# mml_matrix.net
KiCad netlist of a schematic drawn in EAGLE
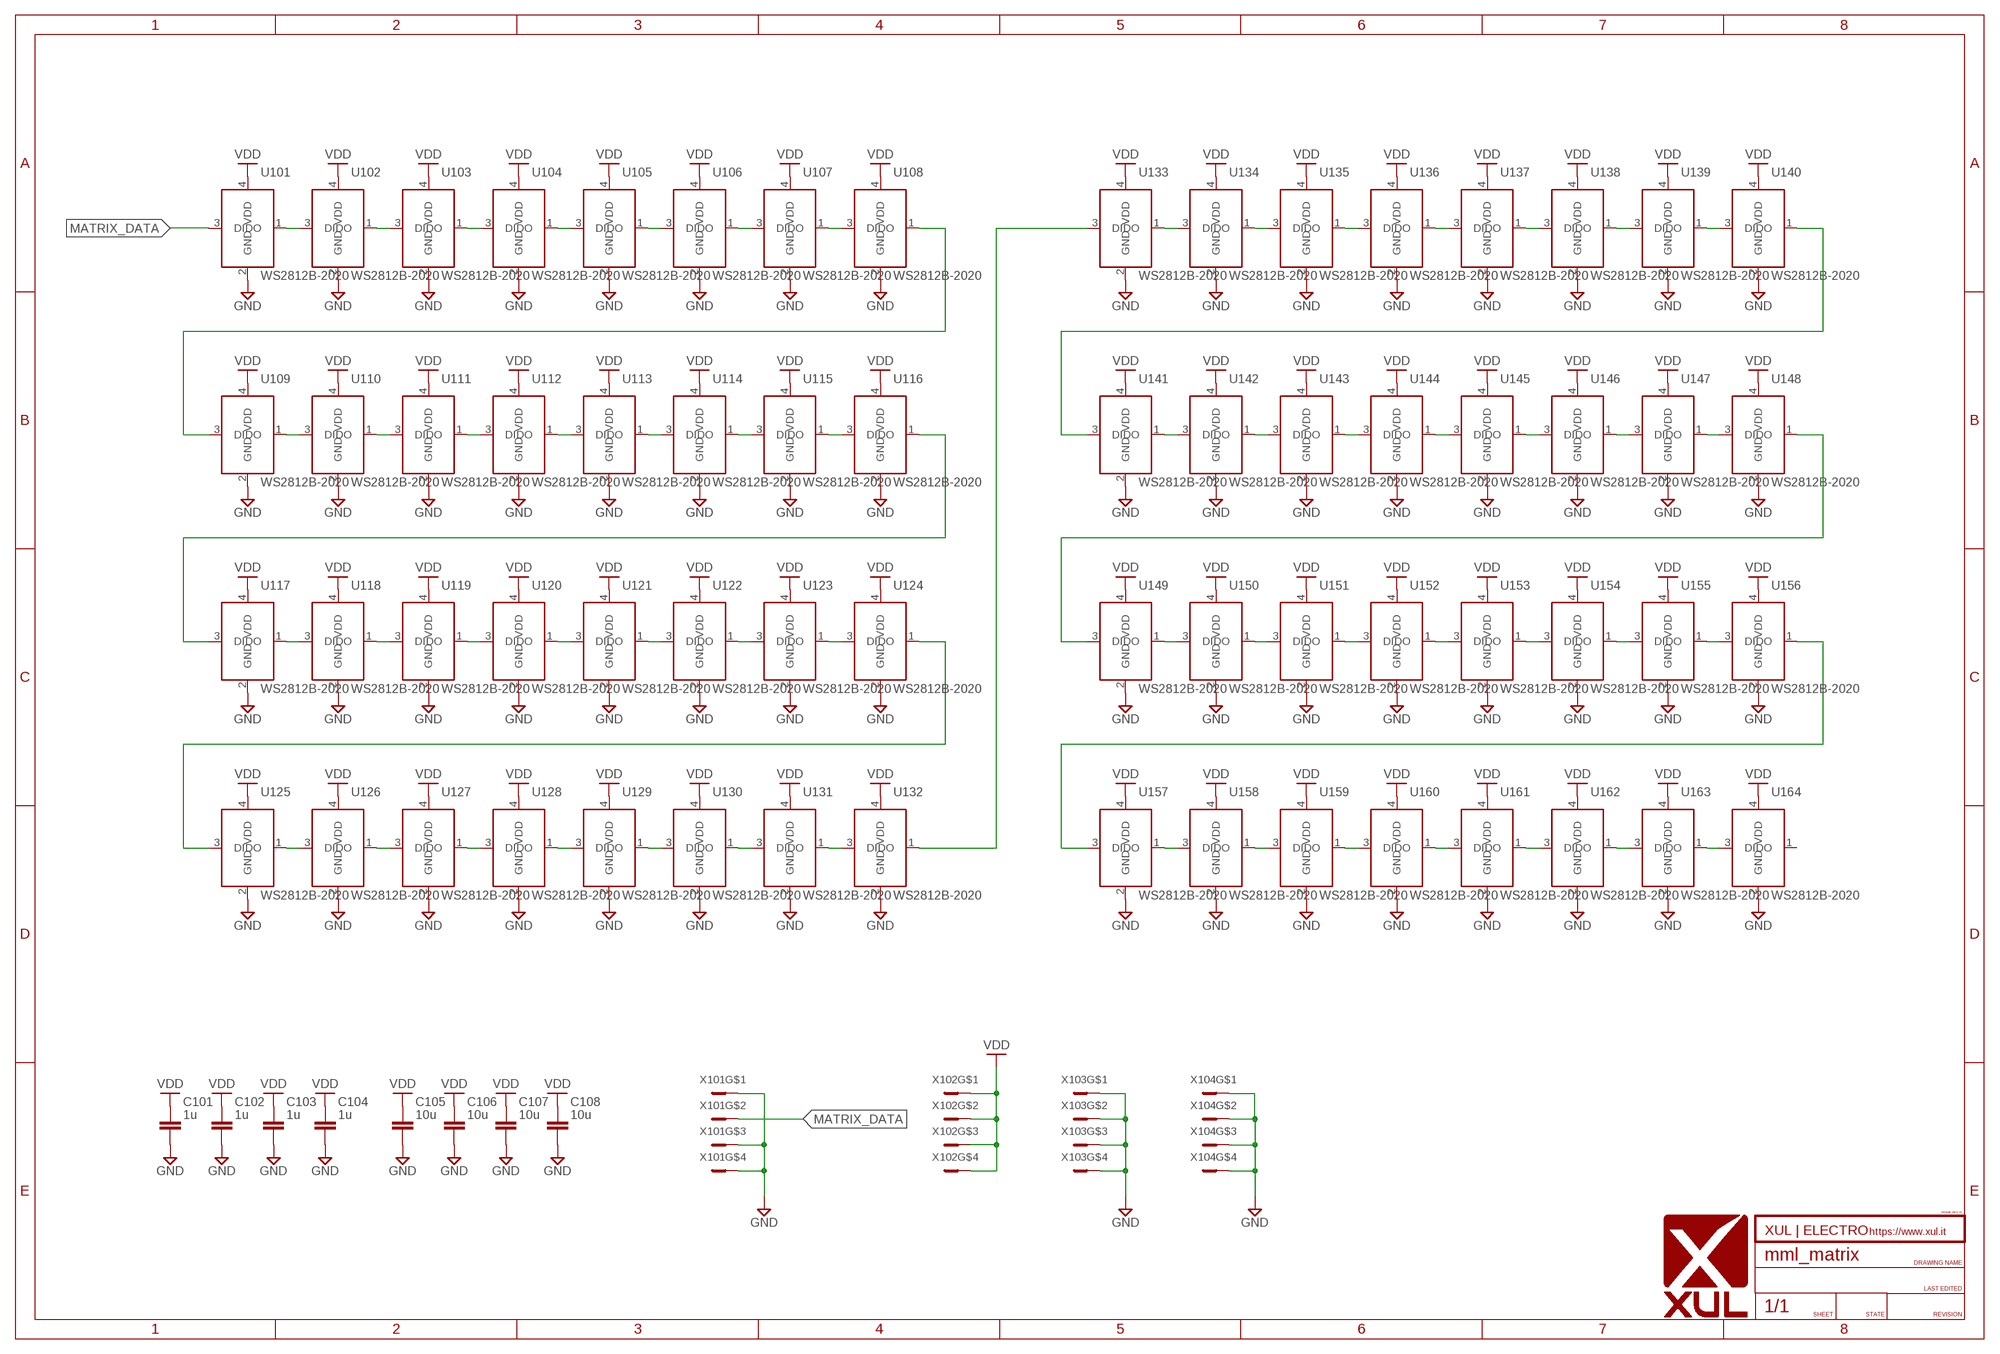
[diagram p0: schematic, sheet 1]

(export (version "E")
  (design (tool "Eeschema 10.0.6"))
  (components
    (comp (ref "C101")
      (value "1u")
      (footprint "eagle-import:CAPC1608X85")
      (libsource (lib "eagle-import") (part "CCHIP-0603(1608-METRIC)_"))
    )
    (comp (ref "C102")
      (value "1u")
      (footprint "eagle-import:CAPC1608X85")
      (libsource (lib "eagle-import") (part "CCHIP-0603(1608-METRIC)_"))
    )
    (comp (ref "C103")
      (value "1u")
      (footprint "eagle-import:CAPC1608X85")
      (libsource (lib "eagle-import") (part "CCHIP-0603(1608-METRIC)_"))
    )
    (comp (ref "C104")
      (value "1u")
      (footprint "eagle-import:CAPC1608X85")
      (libsource (lib "eagle-import") (part "CCHIP-0603(1608-METRIC)_"))
    )
    (comp (ref "C105")
      (value "10u")
      (footprint "eagle-import:CAPC2012X110")
      (libsource (lib "eagle-import") (part "CCHIP-0805(2012-METRIC)_"))
    )
    (comp (ref "C106")
      (value "10u")
      (footprint "eagle-import:CAPC2012X110")
      (libsource (lib "eagle-import") (part "CCHIP-0805(2012-METRIC)_"))
    )
    (comp (ref "C107")
      (value "10u")
      (footprint "eagle-import:CAPC2012X110")
      (libsource (lib "eagle-import") (part "CCHIP-0805(2012-METRIC)_"))
    )
    (comp (ref "C108")
      (value "10u")
      (footprint "eagle-import:CAPC2012X110")
      (libsource (lib "eagle-import") (part "CCHIP-0805(2012-METRIC)_"))
    )
    (comp (ref "U101")
      (value "WS2812B-2020")
      (footprint "eagle-import:RESCAV100P200X220X28-4L")
      (libsource (lib "eagle-import") (part "WS2812B-2020"))
    )
    (comp (ref "U102")
      (value "WS2812B-2020")
      (footprint "eagle-import:RESCAV100P200X220X28-4L")
      (libsource (lib "eagle-import") (part "WS2812B-2020"))
    )
    (comp (ref "U103")
      (value "WS2812B-2020")
      (footprint "eagle-import:RESCAV100P200X220X28-4L")
      (libsource (lib "eagle-import") (part "WS2812B-2020"))
    )
    (comp (ref "U104")
      (value "WS2812B-2020")
      (footprint "eagle-import:RESCAV100P200X220X28-4L")
      (libsource (lib "eagle-import") (part "WS2812B-2020"))
    )
    (comp (ref "U105")
      (value "WS2812B-2020")
      (footprint "eagle-import:RESCAV100P200X220X28-4L")
      (libsource (lib "eagle-import") (part "WS2812B-2020"))
    )
    (comp (ref "U106")
      (value "WS2812B-2020")
      (footprint "eagle-import:RESCAV100P200X220X28-4L")
      (libsource (lib "eagle-import") (part "WS2812B-2020"))
    )
    (comp (ref "U107")
      (value "WS2812B-2020")
      (footprint "eagle-import:RESCAV100P200X220X28-4L")
      (libsource (lib "eagle-import") (part "WS2812B-2020"))
    )
    (comp (ref "U108")
      (value "WS2812B-2020")
      (footprint "eagle-import:RESCAV100P200X220X28-4L")
      (libsource (lib "eagle-import") (part "WS2812B-2020"))
    )
    (comp (ref "U109")
      (value "WS2812B-2020")
      (footprint "eagle-import:RESCAV100P200X220X28-4L")
      (libsource (lib "eagle-import") (part "WS2812B-2020"))
    )
    (comp (ref "U110")
      (value "WS2812B-2020")
      (footprint "eagle-import:RESCAV100P200X220X28-4L")
      (libsource (lib "eagle-import") (part "WS2812B-2020"))
    )
    (comp (ref "U111")
      (value "WS2812B-2020")
      (footprint "eagle-import:RESCAV100P200X220X28-4L")
      (libsource (lib "eagle-import") (part "WS2812B-2020"))
    )
    (comp (ref "U112")
      (value "WS2812B-2020")
      (footprint "eagle-import:RESCAV100P200X220X28-4L")
      (libsource (lib "eagle-import") (part "WS2812B-2020"))
    )
    (comp (ref "U113")
      (value "WS2812B-2020")
      (footprint "eagle-import:RESCAV100P200X220X28-4L")
      (libsource (lib "eagle-import") (part "WS2812B-2020"))
    )
    (comp (ref "U114")
      (value "WS2812B-2020")
      (footprint "eagle-import:RESCAV100P200X220X28-4L")
      (libsource (lib "eagle-import") (part "WS2812B-2020"))
    )
    (comp (ref "U115")
      (value "WS2812B-2020")
      (footprint "eagle-import:RESCAV100P200X220X28-4L")
      (libsource (lib "eagle-import") (part "WS2812B-2020"))
    )
    (comp (ref "U116")
      (value "WS2812B-2020")
      (footprint "eagle-import:RESCAV100P200X220X28-4L")
      (libsource (lib "eagle-import") (part "WS2812B-2020"))
    )
    (comp (ref "U117")
      (value "WS2812B-2020")
      (footprint "eagle-import:RESCAV100P200X220X28-4L")
      (libsource (lib "eagle-import") (part "WS2812B-2020"))
    )
    (comp (ref "U118")
      (value "WS2812B-2020")
      (footprint "eagle-import:RESCAV100P200X220X28-4L")
      (libsource (lib "eagle-import") (part "WS2812B-2020"))
    )
    (comp (ref "U119")
      (value "WS2812B-2020")
      (footprint "eagle-import:RESCAV100P200X220X28-4L")
      (libsource (lib "eagle-import") (part "WS2812B-2020"))
    )
    (comp (ref "U120")
      (value "WS2812B-2020")
      (footprint "eagle-import:RESCAV100P200X220X28-4L")
      (libsource (lib "eagle-import") (part "WS2812B-2020"))
    )
    (comp (ref "U121")
      (value "WS2812B-2020")
      (footprint "eagle-import:RESCAV100P200X220X28-4L")
      (libsource (lib "eagle-import") (part "WS2812B-2020"))
    )
    (comp (ref "U122")
      (value "WS2812B-2020")
      (footprint "eagle-import:RESCAV100P200X220X28-4L")
      (libsource (lib "eagle-import") (part "WS2812B-2020"))
    )
    (comp (ref "U123")
      (value "WS2812B-2020")
      (footprint "eagle-import:RESCAV100P200X220X28-4L")
      (libsource (lib "eagle-import") (part "WS2812B-2020"))
    )
    (comp (ref "U124")
      (value "WS2812B-2020")
      (footprint "eagle-import:RESCAV100P200X220X28-4L")
      (libsource (lib "eagle-import") (part "WS2812B-2020"))
    )
    (comp (ref "U125")
      (value "WS2812B-2020")
      (footprint "eagle-import:RESCAV100P200X220X28-4L")
      (libsource (lib "eagle-import") (part "WS2812B-2020"))
    )
    (comp (ref "U126")
      (value "WS2812B-2020")
      (footprint "eagle-import:RESCAV100P200X220X28-4L")
      (libsource (lib "eagle-import") (part "WS2812B-2020"))
    )
    (comp (ref "U127")
      (value "WS2812B-2020")
      (footprint "eagle-import:RESCAV100P200X220X28-4L")
      (libsource (lib "eagle-import") (part "WS2812B-2020"))
    )
    (comp (ref "U128")
      (value "WS2812B-2020")
      (footprint "eagle-import:RESCAV100P200X220X28-4L")
      (libsource (lib "eagle-import") (part "WS2812B-2020"))
    )
    (comp (ref "U129")
      (value "WS2812B-2020")
      (footprint "eagle-import:RESCAV100P200X220X28-4L")
      (libsource (lib "eagle-import") (part "WS2812B-2020"))
    )
    (comp (ref "U130")
      (value "WS2812B-2020")
      (footprint "eagle-import:RESCAV100P200X220X28-4L")
      (libsource (lib "eagle-import") (part "WS2812B-2020"))
    )
    (comp (ref "U131")
      (value "WS2812B-2020")
      (footprint "eagle-import:RESCAV100P200X220X28-4L")
      (libsource (lib "eagle-import") (part "WS2812B-2020"))
    )
    (comp (ref "U132")
      (value "WS2812B-2020")
      (footprint "eagle-import:RESCAV100P200X220X28-4L")
      (libsource (lib "eagle-import") (part "WS2812B-2020"))
    )
    (comp (ref "U133")
      (value "WS2812B-2020")
      (footprint "eagle-import:RESCAV100P200X220X28-4L")
      (libsource (lib "eagle-import") (part "WS2812B-2020"))
    )
    (comp (ref "U134")
      (value "WS2812B-2020")
      (footprint "eagle-import:RESCAV100P200X220X28-4L")
      (libsource (lib "eagle-import") (part "WS2812B-2020"))
    )
    (comp (ref "U135")
      (value "WS2812B-2020")
      (footprint "eagle-import:RESCAV100P200X220X28-4L")
      (libsource (lib "eagle-import") (part "WS2812B-2020"))
    )
    (comp (ref "U136")
      (value "WS2812B-2020")
      (footprint "eagle-import:RESCAV100P200X220X28-4L")
      (libsource (lib "eagle-import") (part "WS2812B-2020"))
    )
    (comp (ref "U137")
      (value "WS2812B-2020")
      (footprint "eagle-import:RESCAV100P200X220X28-4L")
      (libsource (lib "eagle-import") (part "WS2812B-2020"))
    )
    (comp (ref "U138")
      (value "WS2812B-2020")
      (footprint "eagle-import:RESCAV100P200X220X28-4L")
      (libsource (lib "eagle-import") (part "WS2812B-2020"))
    )
    (comp (ref "U139")
      (value "WS2812B-2020")
      (footprint "eagle-import:RESCAV100P200X220X28-4L")
      (libsource (lib "eagle-import") (part "WS2812B-2020"))
    )
    (comp (ref "U140")
      (value "WS2812B-2020")
      (footprint "eagle-import:RESCAV100P200X220X28-4L")
      (libsource (lib "eagle-import") (part "WS2812B-2020"))
    )
    (comp (ref "U141")
      (value "WS2812B-2020")
      (footprint "eagle-import:RESCAV100P200X220X28-4L")
      (libsource (lib "eagle-import") (part "WS2812B-2020"))
    )
    (comp (ref "U142")
      (value "WS2812B-2020")
      (footprint "eagle-import:RESCAV100P200X220X28-4L")
      (libsource (lib "eagle-import") (part "WS2812B-2020"))
    )
    (comp (ref "U143")
      (value "WS2812B-2020")
      (footprint "eagle-import:RESCAV100P200X220X28-4L")
      (libsource (lib "eagle-import") (part "WS2812B-2020"))
    )
    (comp (ref "U144")
      (value "WS2812B-2020")
      (footprint "eagle-import:RESCAV100P200X220X28-4L")
      (libsource (lib "eagle-import") (part "WS2812B-2020"))
    )
    (comp (ref "U145")
      (value "WS2812B-2020")
      (footprint "eagle-import:RESCAV100P200X220X28-4L")
      (libsource (lib "eagle-import") (part "WS2812B-2020"))
    )
    (comp (ref "U146")
      (value "WS2812B-2020")
      (footprint "eagle-import:RESCAV100P200X220X28-4L")
      (libsource (lib "eagle-import") (part "WS2812B-2020"))
    )
    (comp (ref "U147")
      (value "WS2812B-2020")
      (footprint "eagle-import:RESCAV100P200X220X28-4L")
      (libsource (lib "eagle-import") (part "WS2812B-2020"))
    )
    (comp (ref "U148")
      (value "WS2812B-2020")
      (footprint "eagle-import:RESCAV100P200X220X28-4L")
      (libsource (lib "eagle-import") (part "WS2812B-2020"))
    )
    (comp (ref "U149")
      (value "WS2812B-2020")
      (footprint "eagle-import:RESCAV100P200X220X28-4L")
      (libsource (lib "eagle-import") (part "WS2812B-2020"))
    )
    (comp (ref "U150")
      (value "WS2812B-2020")
      (footprint "eagle-import:RESCAV100P200X220X28-4L")
      (libsource (lib "eagle-import") (part "WS2812B-2020"))
    )
    (comp (ref "U151")
      (value "WS2812B-2020")
      (footprint "eagle-import:RESCAV100P200X220X28-4L")
      (libsource (lib "eagle-import") (part "WS2812B-2020"))
    )
    (comp (ref "U152")
      (value "WS2812B-2020")
      (footprint "eagle-import:RESCAV100P200X220X28-4L")
      (libsource (lib "eagle-import") (part "WS2812B-2020"))
    )
    (comp (ref "U153")
      (value "WS2812B-2020")
      (footprint "eagle-import:RESCAV100P200X220X28-4L")
      (libsource (lib "eagle-import") (part "WS2812B-2020"))
    )
    (comp (ref "U154")
      (value "WS2812B-2020")
      (footprint "eagle-import:RESCAV100P200X220X28-4L")
      (libsource (lib "eagle-import") (part "WS2812B-2020"))
    )
    (comp (ref "U155")
      (value "WS2812B-2020")
      (footprint "eagle-import:RESCAV100P200X220X28-4L")
      (libsource (lib "eagle-import") (part "WS2812B-2020"))
    )
    (comp (ref "U156")
      (value "WS2812B-2020")
      (footprint "eagle-import:RESCAV100P200X220X28-4L")
      (libsource (lib "eagle-import") (part "WS2812B-2020"))
    )
    (comp (ref "U157")
      (value "WS2812B-2020")
      (footprint "eagle-import:RESCAV100P200X220X28-4L")
      (libsource (lib "eagle-import") (part "WS2812B-2020"))
    )
    (comp (ref "U158")
      (value "WS2812B-2020")
      (footprint "eagle-import:RESCAV100P200X220X28-4L")
      (libsource (lib "eagle-import") (part "WS2812B-2020"))
    )
    (comp (ref "U159")
      (value "WS2812B-2020")
      (footprint "eagle-import:RESCAV100P200X220X28-4L")
      (libsource (lib "eagle-import") (part "WS2812B-2020"))
    )
    (comp (ref "U160")
      (value "WS2812B-2020")
      (footprint "eagle-import:RESCAV100P200X220X28-4L")
      (libsource (lib "eagle-import") (part "WS2812B-2020"))
    )
    (comp (ref "U161")
      (value "WS2812B-2020")
      (footprint "eagle-import:RESCAV100P200X220X28-4L")
      (libsource (lib "eagle-import") (part "WS2812B-2020"))
    )
    (comp (ref "U162")
      (value "WS2812B-2020")
      (footprint "eagle-import:RESCAV100P200X220X28-4L")
      (libsource (lib "eagle-import") (part "WS2812B-2020"))
    )
    (comp (ref "U163")
      (value "WS2812B-2020")
      (footprint "eagle-import:RESCAV100P200X220X28-4L")
      (libsource (lib "eagle-import") (part "WS2812B-2020"))
    )
    (comp (ref "U164")
      (value "WS2812B-2020")
      (footprint "eagle-import:RESCAV100P200X220X28-4L")
      (libsource (lib "eagle-import") (part "WS2812B-2020"))
    )
    (comp (ref "X101")
      (value "HW-02-10-T-D-500-SM")
      (footprint "eagle-import:HW-02-10-T-D-500-SM")
      (libsource (lib "eagle-import") (part "HW-02-10-T-D-500-SM"))
    )
    (comp (ref "X102")
      (value "HW-02-10-T-D-500-SM")
      (footprint "eagle-import:HW-02-10-T-D-500-SM")
      (libsource (lib "eagle-import") (part "HW-02-10-T-D-500-SM"))
    )
    (comp (ref "X103")
      (value "HW-02-10-T-D-500-SM")
      (footprint "eagle-import:HW-02-10-T-D-500-SM")
      (libsource (lib "eagle-import") (part "HW-02-10-T-D-500-SM"))
    )
    (comp (ref "X104")
      (value "HW-02-10-T-D-500-SM")
      (footprint "eagle-import:HW-02-10-T-D-500-SM")
      (libsource (lib "eagle-import") (part "HW-02-10-T-D-500-SM"))
    )
  )
  (nets
    (net (code "1") (name "GND") (class "Default")
      (node (ref "C101") (pin "2") (pinfunction "2_2") (pintype "passive"))
      (node (ref "C102") (pin "2") (pinfunction "2_2") (pintype "passive"))
      (node (ref "C103") (pin "2") (pinfunction "2_2") (pintype "passive"))
      (node (ref "C104") (pin "2") (pinfunction "2_2") (pintype "passive"))
      (node (ref "C105") (pin "2") (pinfunction "2_2") (pintype "passive"))
      (node (ref "C106") (pin "2") (pinfunction "2_2") (pintype "passive"))
      (node (ref "C107") (pin "2") (pinfunction "2_2") (pintype "passive"))
      (node (ref "C108") (pin "2") (pinfunction "2_2") (pintype "passive"))
      (node (ref "U101") (pin "2") (pinfunction "GND_2") (pintype "bidirectional"))
      (node (ref "U102") (pin "2") (pinfunction "GND_2") (pintype "bidirectional"))
      (node (ref "U103") (pin "2") (pinfunction "GND_2") (pintype "bidirectional"))
      (node (ref "U104") (pin "2") (pinfunction "GND_2") (pintype "bidirectional"))
      (node (ref "U105") (pin "2") (pinfunction "GND_2") (pintype "bidirectional"))
      (node (ref "U106") (pin "2") (pinfunction "GND_2") (pintype "bidirectional"))
      (node (ref "U107") (pin "2") (pinfunction "GND_2") (pintype "bidirectional"))
      (node (ref "U108") (pin "2") (pinfunction "GND_2") (pintype "bidirectional"))
      (node (ref "U109") (pin "2") (pinfunction "GND_2") (pintype "bidirectional"))
      (node (ref "U110") (pin "2") (pinfunction "GND_2") (pintype "bidirectional"))
      (node (ref "U111") (pin "2") (pinfunction "GND_2") (pintype "bidirectional"))
      (node (ref "U112") (pin "2") (pinfunction "GND_2") (pintype "bidirectional"))
      (node (ref "U113") (pin "2") (pinfunction "GND_2") (pintype "bidirectional"))
      (node (ref "U114") (pin "2") (pinfunction "GND_2") (pintype "bidirectional"))
      (node (ref "U115") (pin "2") (pinfunction "GND_2") (pintype "bidirectional"))
      (node (ref "U116") (pin "2") (pinfunction "GND_2") (pintype "bidirectional"))
      (node (ref "U117") (pin "2") (pinfunction "GND_2") (pintype "bidirectional"))
      (node (ref "U118") (pin "2") (pinfunction "GND_2") (pintype "bidirectional"))
      (node (ref "U119") (pin "2") (pinfunction "GND_2") (pintype "bidirectional"))
      (node (ref "U120") (pin "2") (pinfunction "GND_2") (pintype "bidirectional"))
      (node (ref "U121") (pin "2") (pinfunction "GND_2") (pintype "bidirectional"))
      (node (ref "U122") (pin "2") (pinfunction "GND_2") (pintype "bidirectional"))
      (node (ref "U123") (pin "2") (pinfunction "GND_2") (pintype "bidirectional"))
      (node (ref "U124") (pin "2") (pinfunction "GND_2") (pintype "bidirectional"))
      (node (ref "U125") (pin "2") (pinfunction "GND_2") (pintype "bidirectional"))
      (node (ref "U126") (pin "2") (pinfunction "GND_2") (pintype "bidirectional"))
      (node (ref "U127") (pin "2") (pinfunction "GND_2") (pintype "bidirectional"))
      (node (ref "U128") (pin "2") (pinfunction "GND_2") (pintype "bidirectional"))
      (node (ref "U129") (pin "2") (pinfunction "GND_2") (pintype "bidirectional"))
      (node (ref "U130") (pin "2") (pinfunction "GND_2") (pintype "bidirectional"))
      (node (ref "U131") (pin "2") (pinfunction "GND_2") (pintype "bidirectional"))
      (node (ref "U132") (pin "2") (pinfunction "GND_2") (pintype "bidirectional"))
      (node (ref "U133") (pin "2") (pinfunction "GND_2") (pintype "bidirectional"))
      (node (ref "U134") (pin "2") (pinfunction "GND_2") (pintype "bidirectional"))
      (node (ref "U135") (pin "2") (pinfunction "GND_2") (pintype "bidirectional"))
      (node (ref "U136") (pin "2") (pinfunction "GND_2") (pintype "bidirectional"))
      (node (ref "U137") (pin "2") (pinfunction "GND_2") (pintype "bidirectional"))
      (node (ref "U138") (pin "2") (pinfunction "GND_2") (pintype "bidirectional"))
      (node (ref "U139") (pin "2") (pinfunction "GND_2") (pintype "bidirectional"))
      (node (ref "U140") (pin "2") (pinfunction "GND_2") (pintype "bidirectional"))
      (node (ref "U141") (pin "2") (pinfunction "GND_2") (pintype "bidirectional"))
      (node (ref "U142") (pin "2") (pinfunction "GND_2") (pintype "bidirectional"))
      (node (ref "U143") (pin "2") (pinfunction "GND_2") (pintype "bidirectional"))
      (node (ref "U144") (pin "2") (pinfunction "GND_2") (pintype "bidirectional"))
      (node (ref "U145") (pin "2") (pinfunction "GND_2") (pintype "bidirectional"))
      (node (ref "U146") (pin "2") (pinfunction "GND_2") (pintype "bidirectional"))
      (node (ref "U147") (pin "2") (pinfunction "GND_2") (pintype "bidirectional"))
      (node (ref "U148") (pin "2") (pinfunction "GND_2") (pintype "bidirectional"))
      (node (ref "U149") (pin "2") (pinfunction "GND_2") (pintype "bidirectional"))
      (node (ref "U150") (pin "2") (pinfunction "GND_2") (pintype "bidirectional"))
      (node (ref "U151") (pin "2") (pinfunction "GND_2") (pintype "bidirectional"))
      (node (ref "U152") (pin "2") (pinfunction "GND_2") (pintype "bidirectional"))
      (node (ref "U153") (pin "2") (pinfunction "GND_2") (pintype "bidirectional"))
      (node (ref "U154") (pin "2") (pinfunction "GND_2") (pintype "bidirectional"))
      (node (ref "U155") (pin "2") (pinfunction "GND_2") (pintype "bidirectional"))
      (node (ref "U156") (pin "2") (pinfunction "GND_2") (pintype "bidirectional"))
      (node (ref "U157") (pin "2") (pinfunction "GND_2") (pintype "bidirectional"))
      (node (ref "U158") (pin "2") (pinfunction "GND_2") (pintype "bidirectional"))
      (node (ref "U159") (pin "2") (pinfunction "GND_2") (pintype "bidirectional"))
      (node (ref "U160") (pin "2") (pinfunction "GND_2") (pintype "bidirectional"))
      (node (ref "U161") (pin "2") (pinfunction "GND_2") (pintype "bidirectional"))
      (node (ref "U162") (pin "2") (pinfunction "GND_2") (pintype "bidirectional"))
      (node (ref "U163") (pin "2") (pinfunction "GND_2") (pintype "bidirectional"))
      (node (ref "U164") (pin "2") (pinfunction "GND_2") (pintype "bidirectional"))
      (node (ref "X101") (pin "P$1") (pinfunction "SK_P$1") (pintype "passive"))
      (node (ref "X101") (pin "P$3") (pinfunction "SK_P$3") (pintype "passive"))
      (node (ref "X101") (pin "P$4") (pinfunction "SK_P$4") (pintype "passive"))
      (node (ref "X103") (pin "P$1") (pinfunction "SK_P$1") (pintype "passive"))
      (node (ref "X103") (pin "P$2") (pinfunction "SK_P$2") (pintype "passive"))
      (node (ref "X103") (pin "P$3") (pinfunction "SK_P$3") (pintype "passive"))
      (node (ref "X103") (pin "P$4") (pinfunction "SK_P$4") (pintype "passive"))
      (node (ref "X104") (pin "P$1") (pinfunction "SK_P$1") (pintype "passive"))
      (node (ref "X104") (pin "P$2") (pinfunction "SK_P$2") (pintype "passive"))
      (node (ref "X104") (pin "P$3") (pinfunction "SK_P$3") (pintype "passive"))
      (node (ref "X104") (pin "P$4") (pinfunction "SK_P$4") (pintype "passive"))
    )
    (net (code "2") (name "MATRIX_DATA") (class "Default")
      (node (ref "U101") (pin "3") (pinfunction "DI_3") (pintype "bidirectional"))
      (node (ref "X101") (pin "P$2") (pinfunction "SK_P$2") (pintype "passive"))
    )
    (net (code "3") (name "Net-(U101-DO)") (class "Default")
      (node (ref "U101") (pin "1") (pinfunction "DO_1") (pintype "bidirectional"))
      (node (ref "U102") (pin "3") (pinfunction "DI_3") (pintype "bidirectional"))
    )
    (net (code "4") (name "Net-(U102-DO)") (class "Default")
      (node (ref "U102") (pin "1") (pinfunction "DO_1") (pintype "bidirectional"))
      (node (ref "U103") (pin "3") (pinfunction "DI_3") (pintype "bidirectional"))
    )
    (net (code "5") (name "Net-(U103-DO)") (class "Default")
      (node (ref "U103") (pin "1") (pinfunction "DO_1") (pintype "bidirectional"))
      (node (ref "U104") (pin "3") (pinfunction "DI_3") (pintype "bidirectional"))
    )
    (net (code "6") (name "Net-(U104-DO)") (class "Default")
      (node (ref "U104") (pin "1") (pinfunction "DO_1") (pintype "bidirectional"))
      (node (ref "U105") (pin "3") (pinfunction "DI_3") (pintype "bidirectional"))
    )
    (net (code "7") (name "Net-(U105-DO)") (class "Default")
      (node (ref "U105") (pin "1") (pinfunction "DO_1") (pintype "bidirectional"))
      (node (ref "U106") (pin "3") (pinfunction "DI_3") (pintype "bidirectional"))
    )
    (net (code "8") (name "Net-(U106-DO)") (class "Default")
      (node (ref "U106") (pin "1") (pinfunction "DO_1") (pintype "bidirectional"))
      (node (ref "U107") (pin "3") (pinfunction "DI_3") (pintype "bidirectional"))
    )
    (net (code "9") (name "Net-(U107-DO)") (class "Default")
      (node (ref "U107") (pin "1") (pinfunction "DO_1") (pintype "bidirectional"))
      (node (ref "U108") (pin "3") (pinfunction "DI_3") (pintype "bidirectional"))
    )
    (net (code "10") (name "Net-(U108-DO)") (class "Default")
      (node (ref "U108") (pin "1") (pinfunction "DO_1") (pintype "bidirectional"))
      (node (ref "U109") (pin "3") (pinfunction "DI_3") (pintype "bidirectional"))
    )
    (net (code "11") (name "Net-(U109-DO)") (class "Default")
      (node (ref "U109") (pin "1") (pinfunction "DO_1") (pintype "bidirectional"))
      (node (ref "U110") (pin "3") (pinfunction "DI_3") (pintype "bidirectional"))
    )
    (net (code "12") (name "Net-(U110-DO)") (class "Default")
      (node (ref "U110") (pin "1") (pinfunction "DO_1") (pintype "bidirectional"))
      (node (ref "U111") (pin "3") (pinfunction "DI_3") (pintype "bidirectional"))
    )
    (net (code "13") (name "Net-(U111-DO)") (class "Default")
      (node (ref "U111") (pin "1") (pinfunction "DO_1") (pintype "bidirectional"))
      (node (ref "U112") (pin "3") (pinfunction "DI_3") (pintype "bidirectional"))
    )
    (net (code "14") (name "Net-(U112-DO)") (class "Default")
      (node (ref "U112") (pin "1") (pinfunction "DO_1") (pintype "bidirectional"))
      (node (ref "U113") (pin "3") (pinfunction "DI_3") (pintype "bidirectional"))
    )
    (net (code "15") (name "Net-(U113-DO)") (class "Default")
      (node (ref "U113") (pin "1") (pinfunction "DO_1") (pintype "bidirectional"))
      (node (ref "U114") (pin "3") (pinfunction "DI_3") (pintype "bidirectional"))
    )
    (net (code "16") (name "Net-(U114-DO)") (class "Default")
      (node (ref "U114") (pin "1") (pinfunction "DO_1") (pintype "bidirectional"))
      (node (ref "U115") (pin "3") (pinfunction "DI_3") (pintype "bidirectional"))
    )
    (net (code "17") (name "Net-(U115-DO)") (class "Default")
      (node (ref "U115") (pin "1") (pinfunction "DO_1") (pintype "bidirectional"))
      (node (ref "U116") (pin "3") (pinfunction "DI_3") (pintype "bidirectional"))
    )
    (net (code "18") (name "Net-(U116-DO)") (class "Default")
      (node (ref "U116") (pin "1") (pinfunction "DO_1") (pintype "bidirectional"))
      (node (ref "U117") (pin "3") (pinfunction "DI_3") (pintype "bidirectional"))
    )
    (net (code "19") (name "Net-(U117-DO)") (class "Default")
      (node (ref "U117") (pin "1") (pinfunction "DO_1") (pintype "bidirectional"))
      (node (ref "U118") (pin "3") (pinfunction "DI_3") (pintype "bidirectional"))
    )
    (net (code "20") (name "Net-(U118-DO)") (class "Default")
      (node (ref "U118") (pin "1") (pinfunction "DO_1") (pintype "bidirectional"))
      (node (ref "U119") (pin "3") (pinfunction "DI_3") (pintype "bidirectional"))
    )
    (net (code "21") (name "Net-(U119-DO)") (class "Default")
      (node (ref "U119") (pin "1") (pinfunction "DO_1") (pintype "bidirectional"))
      (node (ref "U120") (pin "3") (pinfunction "DI_3") (pintype "bidirectional"))
    )
    (net (code "22") (name "Net-(U120-DO)") (class "Default")
      (node (ref "U120") (pin "1") (pinfunction "DO_1") (pintype "bidirectional"))
      (node (ref "U121") (pin "3") (pinfunction "DI_3") (pintype "bidirectional"))
    )
    (net (code "23") (name "Net-(U121-DO)") (class "Default")
      (node (ref "U121") (pin "1") (pinfunction "DO_1") (pintype "bidirectional"))
      (node (ref "U122") (pin "3") (pinfunction "DI_3") (pintype "bidirectional"))
    )
    (net (code "24") (name "Net-(U122-DO)") (class "Default")
      (node (ref "U122") (pin "1") (pinfunction "DO_1") (pintype "bidirectional"))
      (node (ref "U123") (pin "3") (pinfunction "DI_3") (pintype "bidirectional"))
    )
    (net (code "25") (name "Net-(U123-DO)") (class "Default")
      (node (ref "U123") (pin "1") (pinfunction "DO_1") (pintype "bidirectional"))
      (node (ref "U124") (pin "3") (pinfunction "DI_3") (pintype "bidirectional"))
    )
    (net (code "26") (name "Net-(U124-DO)") (class "Default")
      (node (ref "U124") (pin "1") (pinfunction "DO_1") (pintype "bidirectional"))
      (node (ref "U125") (pin "3") (pinfunction "DI_3") (pintype "bidirectional"))
    )
    (net (code "27") (name "Net-(U125-DO)") (class "Default")
      (node (ref "U125") (pin "1") (pinfunction "DO_1") (pintype "bidirectional"))
      (node (ref "U126") (pin "3") (pinfunction "DI_3") (pintype "bidirectional"))
    )
    (net (code "28") (name "Net-(U126-DO)") (class "Default")
      (node (ref "U126") (pin "1") (pinfunction "DO_1") (pintype "bidirectional"))
      (node (ref "U127") (pin "3") (pinfunction "DI_3") (pintype "bidirectional"))
    )
    (net (code "29") (name "Net-(U127-DO)") (class "Default")
      (node (ref "U127") (pin "1") (pinfunction "DO_1") (pintype "bidirectional"))
      (node (ref "U128") (pin "3") (pinfunction "DI_3") (pintype "bidirectional"))
    )
    (net (code "30") (name "Net-(U128-DO)") (class "Default")
      (node (ref "U128") (pin "1") (pinfunction "DO_1") (pintype "bidirectional"))
      (node (ref "U129") (pin "3") (pinfunction "DI_3") (pintype "bidirectional"))
    )
    (net (code "31") (name "Net-(U129-DO)") (class "Default")
      (node (ref "U129") (pin "1") (pinfunction "DO_1") (pintype "bidirectional"))
      (node (ref "U130") (pin "3") (pinfunction "DI_3") (pintype "bidirectional"))
    )
    (net (code "32") (name "Net-(U130-DO)") (class "Default")
      (node (ref "U130") (pin "1") (pinfunction "DO_1") (pintype "bidirectional"))
      (node (ref "U131") (pin "3") (pinfunction "DI_3") (pintype "bidirectional"))
    )
    (net (code "33") (name "Net-(U131-DO)") (class "Default")
      (node (ref "U131") (pin "1") (pinfunction "DO_1") (pintype "bidirectional"))
      (node (ref "U132") (pin "3") (pinfunction "DI_3") (pintype "bidirectional"))
    )
    (net (code "34") (name "Net-(U132-DO)") (class "Default")
      (node (ref "U132") (pin "1") (pinfunction "DO_1") (pintype "bidirectional"))
      (node (ref "U133") (pin "3") (pinfunction "DI_3") (pintype "bidirectional"))
    )
    (net (code "35") (name "Net-(U133-DO)") (class "Default")
      (node (ref "U133") (pin "1") (pinfunction "DO_1") (pintype "bidirectional"))
      (node (ref "U134") (pin "3") (pinfunction "DI_3") (pintype "bidirectional"))
    )
    (net (code "36") (name "Net-(U134-DO)") (class "Default")
      (node (ref "U134") (pin "1") (pinfunction "DO_1") (pintype "bidirectional"))
      (node (ref "U135") (pin "3") (pinfunction "DI_3") (pintype "bidirectional"))
    )
    (net (code "37") (name "Net-(U135-DO)") (class "Default")
      (node (ref "U135") (pin "1") (pinfunction "DO_1") (pintype "bidirectional"))
      (node (ref "U136") (pin "3") (pinfunction "DI_3") (pintype "bidirectional"))
    )
    (net (code "38") (name "Net-(U136-DO)") (class "Default")
      (node (ref "U136") (pin "1") (pinfunction "DO_1") (pintype "bidirectional"))
      (node (ref "U137") (pin "3") (pinfunction "DI_3") (pintype "bidirectional"))
    )
    (net (code "39") (name "Net-(U137-DO)") (class "Default")
      (node (ref "U137") (pin "1") (pinfunction "DO_1") (pintype "bidirectional"))
      (node (ref "U138") (pin "3") (pinfunction "DI_3") (pintype "bidirectional"))
    )
    (net (code "40") (name "Net-(U138-DO)") (class "Default")
      (node (ref "U138") (pin "1") (pinfunction "DO_1") (pintype "bidirectional"))
      (node (ref "U139") (pin "3") (pinfunction "DI_3") (pintype "bidirectional"))
    )
    (net (code "41") (name "Net-(U139-DO)") (class "Default")
      (node (ref "U139") (pin "1") (pinfunction "DO_1") (pintype "bidirectional"))
      (node (ref "U140") (pin "3") (pinfunction "DI_3") (pintype "bidirectional"))
    )
    (net (code "42") (name "Net-(U140-DO)") (class "Default")
      (node (ref "U140") (pin "1") (pinfunction "DO_1") (pintype "bidirectional"))
      (node (ref "U141") (pin "3") (pinfunction "DI_3") (pintype "bidirectional"))
    )
    (net (code "43") (name "Net-(U141-DO)") (class "Default")
      (node (ref "U141") (pin "1") (pinfunction "DO_1") (pintype "bidirectional"))
      (node (ref "U142") (pin "3") (pinfunction "DI_3") (pintype "bidirectional"))
    )
    (net (code "44") (name "Net-(U142-DO)") (class "Default")
      (node (ref "U142") (pin "1") (pinfunction "DO_1") (pintype "bidirectional"))
      (node (ref "U143") (pin "3") (pinfunction "DI_3") (pintype "bidirectional"))
    )
    (net (code "45") (name "Net-(U143-DO)") (class "Default")
      (node (ref "U143") (pin "1") (pinfunction "DO_1") (pintype "bidirectional"))
      (node (ref "U144") (pin "3") (pinfunction "DI_3") (pintype "bidirectional"))
    )
    (net (code "46") (name "Net-(U144-DO)") (class "Default")
      (node (ref "U144") (pin "1") (pinfunction "DO_1") (pintype "bidirectional"))
      (node (ref "U145") (pin "3") (pinfunction "DI_3") (pintype "bidirectional"))
    )
    (net (code "47") (name "Net-(U145-DO)") (class "Default")
      (node (ref "U145") (pin "1") (pinfunction "DO_1") (pintype "bidirectional"))
      (node (ref "U146") (pin "3") (pinfunction "DI_3") (pintype "bidirectional"))
    )
    (net (code "48") (name "Net-(U146-DO)") (class "Default")
      (node (ref "U146") (pin "1") (pinfunction "DO_1") (pintype "bidirectional"))
      (node (ref "U147") (pin "3") (pinfunction "DI_3") (pintype "bidirectional"))
    )
    (net (code "49") (name "Net-(U147-DO)") (class "Default")
      (node (ref "U147") (pin "1") (pinfunction "DO_1") (pintype "bidirectional"))
      (node (ref "U148") (pin "3") (pinfunction "DI_3") (pintype "bidirectional"))
    )
    (net (code "50") (name "Net-(U148-DO)") (class "Default")
      (node (ref "U148") (pin "1") (pinfunction "DO_1") (pintype "bidirectional"))
      (node (ref "U149") (pin "3") (pinfunction "DI_3") (pintype "bidirectional"))
    )
    (net (code "51") (name "Net-(U149-DO)") (class "Default")
      (node (ref "U149") (pin "1") (pinfunction "DO_1") (pintype "bidirectional"))
      (node (ref "U150") (pin "3") (pinfunction "DI_3") (pintype "bidirectional"))
    )
    (net (code "52") (name "Net-(U150-DO)") (class "Default")
      (node (ref "U150") (pin "1") (pinfunction "DO_1") (pintype "bidirectional"))
      (node (ref "U151") (pin "3") (pinfunction "DI_3") (pintype "bidirectional"))
    )
    (net (code "53") (name "Net-(U151-DO)") (class "Default")
      (node (ref "U151") (pin "1") (pinfunction "DO_1") (pintype "bidirectional"))
      (node (ref "U152") (pin "3") (pinfunction "DI_3") (pintype "bidirectional"))
    )
    (net (code "54") (name "Net-(U152-DO)") (class "Default")
      (node (ref "U152") (pin "1") (pinfunction "DO_1") (pintype "bidirectional"))
      (node (ref "U153") (pin "3") (pinfunction "DI_3") (pintype "bidirectional"))
    )
    (net (code "55") (name "Net-(U153-DO)") (class "Default")
      (node (ref "U153") (pin "1") (pinfunction "DO_1") (pintype "bidirectional"))
      (node (ref "U154") (pin "3") (pinfunction "DI_3") (pintype "bidirectional"))
    )
    (net (code "56") (name "Net-(U154-DO)") (class "Default")
      (node (ref "U154") (pin "1") (pinfunction "DO_1") (pintype "bidirectional"))
      (node (ref "U155") (pin "3") (pinfunction "DI_3") (pintype "bidirectional"))
    )
    (net (code "57") (name "Net-(U155-DO)") (class "Default")
      (node (ref "U155") (pin "1") (pinfunction "DO_1") (pintype "bidirectional"))
      (node (ref "U156") (pin "3") (pinfunction "DI_3") (pintype "bidirectional"))
    )
    (net (code "58") (name "Net-(U156-DO)") (class "Default")
      (node (ref "U156") (pin "1") (pinfunction "DO_1") (pintype "bidirectional"))
      (node (ref "U157") (pin "3") (pinfunction "DI_3") (pintype "bidirectional"))
    )
    (net (code "59") (name "Net-(U157-DO)") (class "Default")
      (node (ref "U157") (pin "1") (pinfunction "DO_1") (pintype "bidirectional"))
      (node (ref "U158") (pin "3") (pinfunction "DI_3") (pintype "bidirectional"))
    )
    (net (code "60") (name "Net-(U158-DO)") (class "Default")
      (node (ref "U158") (pin "1") (pinfunction "DO_1") (pintype "bidirectional"))
      (node (ref "U159") (pin "3") (pinfunction "DI_3") (pintype "bidirectional"))
    )
    (net (code "61") (name "Net-(U159-DO)") (class "Default")
      (node (ref "U159") (pin "1") (pinfunction "DO_1") (pintype "bidirectional"))
      (node (ref "U160") (pin "3") (pinfunction "DI_3") (pintype "bidirectional"))
    )
    (net (code "62") (name "Net-(U160-DO)") (class "Default")
      (node (ref "U160") (pin "1") (pinfunction "DO_1") (pintype "bidirectional"))
      (node (ref "U161") (pin "3") (pinfunction "DI_3") (pintype "bidirectional"))
    )
    (net (code "63") (name "Net-(U161-DO)") (class "Default")
      (node (ref "U161") (pin "1") (pinfunction "DO_1") (pintype "bidirectional"))
      (node (ref "U162") (pin "3") (pinfunction "DI_3") (pintype "bidirectional"))
    )
    (net (code "64") (name "Net-(U162-DO)") (class "Default")
      (node (ref "U162") (pin "1") (pinfunction "DO_1") (pintype "bidirectional"))
      (node (ref "U163") (pin "3") (pinfunction "DI_3") (pintype "bidirectional"))
    )
    (net (code "65") (name "Net-(U163-DO)") (class "Default")
      (node (ref "U163") (pin "1") (pinfunction "DO_1") (pintype "bidirectional"))
      (node (ref "U164") (pin "3") (pinfunction "DI_3") (pintype "bidirectional"))
    )
    (net (code "66") (name "VDD") (class "Default")
      (node (ref "C101") (pin "1") (pinfunction "1_1") (pintype "passive"))
      (node (ref "C102") (pin "1") (pinfunction "1_1") (pintype "passive"))
      (node (ref "C103") (pin "1") (pinfunction "1_1") (pintype "passive"))
      (node (ref "C104") (pin "1") (pinfunction "1_1") (pintype "passive"))
      (node (ref "C105") (pin "1") (pinfunction "1_1") (pintype "passive"))
      (node (ref "C106") (pin "1") (pinfunction "1_1") (pintype "passive"))
      (node (ref "C107") (pin "1") (pinfunction "1_1") (pintype "passive"))
      (node (ref "C108") (pin "1") (pinfunction "1_1") (pintype "passive"))
      (node (ref "U101") (pin "4") (pinfunction "VDD_4") (pintype "bidirectional"))
      (node (ref "U102") (pin "4") (pinfunction "VDD_4") (pintype "bidirectional"))
      (node (ref "U103") (pin "4") (pinfunction "VDD_4") (pintype "bidirectional"))
      (node (ref "U104") (pin "4") (pinfunction "VDD_4") (pintype "bidirectional"))
      (node (ref "U105") (pin "4") (pinfunction "VDD_4") (pintype "bidirectional"))
      (node (ref "U106") (pin "4") (pinfunction "VDD_4") (pintype "bidirectional"))
      (node (ref "U107") (pin "4") (pinfunction "VDD_4") (pintype "bidirectional"))
      (node (ref "U108") (pin "4") (pinfunction "VDD_4") (pintype "bidirectional"))
      (node (ref "U109") (pin "4") (pinfunction "VDD_4") (pintype "bidirectional"))
      (node (ref "U110") (pin "4") (pinfunction "VDD_4") (pintype "bidirectional"))
      (node (ref "U111") (pin "4") (pinfunction "VDD_4") (pintype "bidirectional"))
      (node (ref "U112") (pin "4") (pinfunction "VDD_4") (pintype "bidirectional"))
      (node (ref "U113") (pin "4") (pinfunction "VDD_4") (pintype "bidirectional"))
      (node (ref "U114") (pin "4") (pinfunction "VDD_4") (pintype "bidirectional"))
      (node (ref "U115") (pin "4") (pinfunction "VDD_4") (pintype "bidirectional"))
      (node (ref "U116") (pin "4") (pinfunction "VDD_4") (pintype "bidirectional"))
      (node (ref "U117") (pin "4") (pinfunction "VDD_4") (pintype "bidirectional"))
      (node (ref "U118") (pin "4") (pinfunction "VDD_4") (pintype "bidirectional"))
      (node (ref "U119") (pin "4") (pinfunction "VDD_4") (pintype "bidirectional"))
      (node (ref "U120") (pin "4") (pinfunction "VDD_4") (pintype "bidirectional"))
      (node (ref "U121") (pin "4") (pinfunction "VDD_4") (pintype "bidirectional"))
      (node (ref "U122") (pin "4") (pinfunction "VDD_4") (pintype "bidirectional"))
      (node (ref "U123") (pin "4") (pinfunction "VDD_4") (pintype "bidirectional"))
      (node (ref "U124") (pin "4") (pinfunction "VDD_4") (pintype "bidirectional"))
      (node (ref "U125") (pin "4") (pinfunction "VDD_4") (pintype "bidirectional"))
      (node (ref "U126") (pin "4") (pinfunction "VDD_4") (pintype "bidirectional"))
      (node (ref "U127") (pin "4") (pinfunction "VDD_4") (pintype "bidirectional"))
      (node (ref "U128") (pin "4") (pinfunction "VDD_4") (pintype "bidirectional"))
      (node (ref "U129") (pin "4") (pinfunction "VDD_4") (pintype "bidirectional"))
      (node (ref "U130") (pin "4") (pinfunction "VDD_4") (pintype "bidirectional"))
      (node (ref "U131") (pin "4") (pinfunction "VDD_4") (pintype "bidirectional"))
      (node (ref "U132") (pin "4") (pinfunction "VDD_4") (pintype "bidirectional"))
      (node (ref "U133") (pin "4") (pinfunction "VDD_4") (pintype "bidirectional"))
      (node (ref "U134") (pin "4") (pinfunction "VDD_4") (pintype "bidirectional"))
      (node (ref "U135") (pin "4") (pinfunction "VDD_4") (pintype "bidirectional"))
      (node (ref "U136") (pin "4") (pinfunction "VDD_4") (pintype "bidirectional"))
      (node (ref "U137") (pin "4") (pinfunction "VDD_4") (pintype "bidirectional"))
      (node (ref "U138") (pin "4") (pinfunction "VDD_4") (pintype "bidirectional"))
      (node (ref "U139") (pin "4") (pinfunction "VDD_4") (pintype "bidirectional"))
      (node (ref "U140") (pin "4") (pinfunction "VDD_4") (pintype "bidirectional"))
      (node (ref "U141") (pin "4") (pinfunction "VDD_4") (pintype "bidirectional"))
      (node (ref "U142") (pin "4") (pinfunction "VDD_4") (pintype "bidirectional"))
      (node (ref "U143") (pin "4") (pinfunction "VDD_4") (pintype "bidirectional"))
      (node (ref "U144") (pin "4") (pinfunction "VDD_4") (pintype "bidirectional"))
      (node (ref "U145") (pin "4") (pinfunction "VDD_4") (pintype "bidirectional"))
      (node (ref "U146") (pin "4") (pinfunction "VDD_4") (pintype "bidirectional"))
      (node (ref "U147") (pin "4") (pinfunction "VDD_4") (pintype "bidirectional"))
      (node (ref "U148") (pin "4") (pinfunction "VDD_4") (pintype "bidirectional"))
      (node (ref "U149") (pin "4") (pinfunction "VDD_4") (pintype "bidirectional"))
      (node (ref "U150") (pin "4") (pinfunction "VDD_4") (pintype "bidirectional"))
      (node (ref "U151") (pin "4") (pinfunction "VDD_4") (pintype "bidirectional"))
      (node (ref "U152") (pin "4") (pinfunction "VDD_4") (pintype "bidirectional"))
      (node (ref "U153") (pin "4") (pinfunction "VDD_4") (pintype "bidirectional"))
      (node (ref "U154") (pin "4") (pinfunction "VDD_4") (pintype "bidirectional"))
      (node (ref "U155") (pin "4") (pinfunction "VDD_4") (pintype "bidirectional"))
      (node (ref "U156") (pin "4") (pinfunction "VDD_4") (pintype "bidirectional"))
      (node (ref "U157") (pin "4") (pinfunction "VDD_4") (pintype "bidirectional"))
      (node (ref "U158") (pin "4") (pinfunction "VDD_4") (pintype "bidirectional"))
      (node (ref "U159") (pin "4") (pinfunction "VDD_4") (pintype "bidirectional"))
      (node (ref "U160") (pin "4") (pinfunction "VDD_4") (pintype "bidirectional"))
      (node (ref "U161") (pin "4") (pinfunction "VDD_4") (pintype "bidirectional"))
      (node (ref "U162") (pin "4") (pinfunction "VDD_4") (pintype "bidirectional"))
      (node (ref "U163") (pin "4") (pinfunction "VDD_4") (pintype "bidirectional"))
      (node (ref "U164") (pin "4") (pinfunction "VDD_4") (pintype "bidirectional"))
      (node (ref "X102") (pin "P$1") (pinfunction "SK_P$1") (pintype "passive"))
      (node (ref "X102") (pin "P$2") (pinfunction "SK_P$2") (pintype "passive"))
      (node (ref "X102") (pin "P$3") (pinfunction "SK_P$3") (pintype "passive"))
      (node (ref "X102") (pin "P$4") (pinfunction "SK_P$4") (pintype "passive"))
    )
    (net (code "67") (name "unconnected-(U164-DO-Pad1)") (class "Default")
      (node (ref "U164") (pin "1") (pinfunction "DO_1") (pintype "bidirectional"))
    )
  )
)
